# Sheet1.net
KiCad netlist of a schematic drawn in Altium Designer
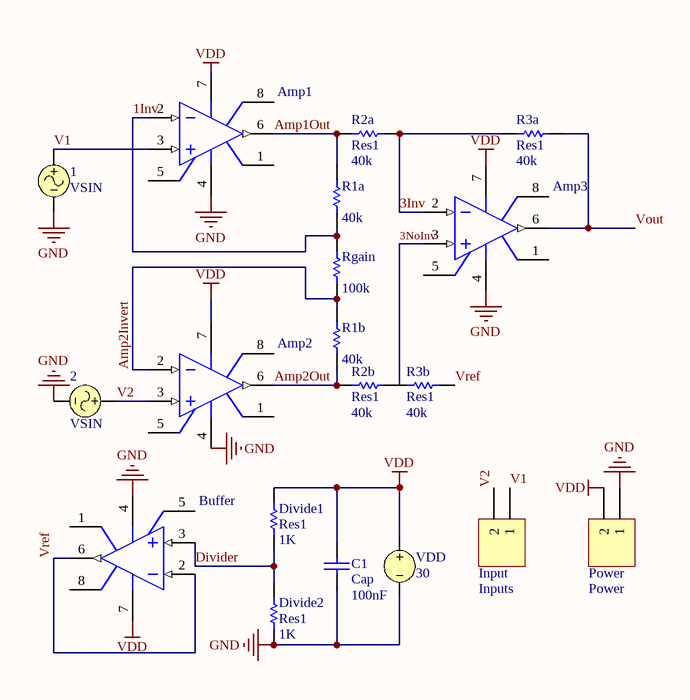
[diagram p0: Sheet1.SchDoc]

(export (version "E")
  (design (tool "Eeschema 10.0.6"))
  (components
    (comp (ref "1")
      (value "VSIN")
      (description "Sinusoidal Voltage Source")
      (fields (field (name "PUBLISHER") "Altium Limited"))
      (libsource (lib "Simulation Sources") (part "VSIN"))
    )
    (comp (ref "2")
      (value "VSIN")
      (description "Sinusoidal Voltage Source")
      (fields (field (name "PUBLISHER") "Altium Limited"))
      (libsource (lib "Simulation Sources") (part "VSIN"))
    )
    (comp (ref "Amp1")
      (value "Op Amp")
      (footprint "H-08A")
      (description "FET Operational Amplifier")
      (fields (field (name "PUBLISHER") "Altium Limited"))
      (libsource (lib "Miscellaneous Devices") (part "Op Amp"))
    )
    (comp (ref "Amp2")
      (value "Op Amp")
      (footprint "H-08A")
      (description "FET Operational Amplifier")
      (fields (field (name "PUBLISHER") "Altium Limited"))
      (libsource (lib "Miscellaneous Devices") (part "Op Amp"))
    )
    (comp (ref "Amp3")
      (value "Op Amp")
      (footprint "H-08A")
      (description "FET Operational Amplifier")
      (fields (field (name "PUBLISHER") "Altium Limited"))
      (libsource (lib "Miscellaneous Devices") (part "Op Amp"))
    )
    (comp (ref "Buffer")
      (value "Op Amp")
      (footprint "H-08A")
      (description "FET Operational Amplifier")
      (fields (field (name "PUBLISHER") "Altium Limited"))
      (libsource (lib "Miscellaneous Devices") (part "Op Amp"))
    )
    (comp (ref "C1")
      (value "Cap")
      (footprint "RAD-0.3")
      (description "Capacitor")
      (fields (field (name "ALTIUM_VALUE") "100nF") (field (name "PUBLISHER") "Altium Limited"))
      (libsource (lib "Miscellaneous Devices") (part "Cap"))
    )
    (comp (ref "Divide1")
      (value "Res1")
      (footprint "AXIAL-0.3")
      (description "Resistor")
      (fields (field (name "ALTIUM_VALUE") "1K") (field (name "PUBLISHER") "Altium Limited"))
      (libsource (lib "Miscellaneous Devices") (part "Res1"))
    )
    (comp (ref "Divide2")
      (value "Res1")
      (footprint "AXIAL-0.3")
      (description "Resistor")
      (fields (field (name "ALTIUM_VALUE") "1K") (field (name "PUBLISHER") "Altium Limited"))
      (libsource (lib "Miscellaneous Devices") (part "Res1"))
    )
    (comp (ref "Input")
      (value "Inputs")
      (footprint "HDR1X2")
      (description "Header, 2-Pin")
      (fields (field (name "PUBLISHER") "Altium Limited"))
      (libsource (lib "Miscellaneous Connectors") (part "Header 2"))
    )
    (comp (ref "Power")
      (value "Power")
      (footprint "HDR1X2")
      (description "Header, 2-Pin")
      (fields (field (name "PUBLISHER") "Altium Limited"))
      (libsource (lib "Miscellaneous Connectors") (part "Header 2"))
    )
    (comp (ref "R1a")
      (value "40k")
      (footprint "AXIAL-0.3")
      (description "Resistor")
      (fields (field (name "PUBLISHER") "Altium Limited"))
      (libsource (lib "Miscellaneous Devices") (part "Res1"))
    )
    (comp (ref "R1b")
      (value "40k")
      (footprint "AXIAL-0.3")
      (description "Resistor")
      (fields (field (name "PUBLISHER") "Altium Limited"))
      (libsource (lib "Miscellaneous Devices") (part "Res1"))
    )
    (comp (ref "R2a")
      (value "Res1")
      (footprint "AXIAL-0.3")
      (description "Resistor")
      (fields (field (name "ALTIUM_VALUE") "40k") (field (name "PUBLISHER") "Altium Limited"))
      (libsource (lib "Miscellaneous Devices") (part "Res1"))
    )
    (comp (ref "R2b")
      (value "Res1")
      (footprint "AXIAL-0.3")
      (description "Resistor")
      (fields (field (name "ALTIUM_VALUE") "40k") (field (name "PUBLISHER") "Altium Limited"))
      (libsource (lib "Miscellaneous Devices") (part "Res1"))
    )
    (comp (ref "R3a")
      (value "Res1")
      (footprint "AXIAL-0.3")
      (description "Resistor")
      (fields (field (name "ALTIUM_VALUE") "40k") (field (name "PUBLISHER") "Altium Limited"))
      (libsource (lib "Miscellaneous Devices") (part "Res1"))
    )
    (comp (ref "R3b")
      (value "Res1")
      (footprint "AXIAL-0.3")
      (description "Resistor")
      (fields (field (name "ALTIUM_VALUE") "40k") (field (name "PUBLISHER") "Altium Limited"))
      (libsource (lib "Miscellaneous Devices") (part "Res1"))
    )
    (comp (ref "Rgain")
      (value "100k")
      (footprint "AXIAL-0.3")
      (description "Resistor")
      (fields (field (name "PUBLISHER") "Altium Limited"))
      (libsource (lib "Miscellaneous Devices") (part "Res1"))
    )
    (comp (ref "VDD")
      (value "30")
      (description "Voltage Source")
      (fields (field (name "PUBLISHER") "Altium Limited"))
      (libsource (lib "Simulation Sources") (part "VSRC"))
    )
  )
  (nets
    (net (code "1") (name "/1Inv") (class "Default")
      (node (ref "Amp1") (pin "2") (pinfunction "IN-_2") (pintype "input"))
      (node (ref "R1a") (pin "1") (pinfunction "1_1") (pintype "passive"))
      (node (ref "Rgain") (pin "2") (pinfunction "2_2") (pintype "passive"))
    )
    (net (code "2") (name "/3Inv") (class "Default")
      (node (ref "Amp3") (pin "2") (pinfunction "IN-_2") (pintype "input"))
      (node (ref "R2a") (pin "2") (pinfunction "2_2") (pintype "passive"))
      (node (ref "R3a") (pin "1") (pinfunction "1_1") (pintype "passive"))
    )
    (net (code "3") (name "/3NoInv") (class "Default")
      (node (ref "Amp3") (pin "3") (pinfunction "IN+_3") (pintype "input"))
      (node (ref "R2b") (pin "2") (pinfunction "2_2") (pintype "passive"))
    )
    (net (code "4") (name "/Amp1Out") (class "Default")
      (node (ref "Amp1") (pin "6") (pinfunction "OUT_6") (pintype "output"))
      (node (ref "R1a") (pin "2") (pinfunction "2_2") (pintype "passive"))
      (node (ref "R2a") (pin "1") (pinfunction "1_1") (pintype "passive"))
    )
    (net (code "5") (name "/Amp2Invert") (class "Default")
      (node (ref "Amp2") (pin "2") (pinfunction "IN-_2") (pintype "input"))
      (node (ref "R1b") (pin "2") (pinfunction "2_2") (pintype "passive"))
      (node (ref "Rgain") (pin "1") (pinfunction "1_1") (pintype "passive"))
    )
    (net (code "6") (name "/Amp2Out") (class "Default")
      (node (ref "Amp2") (pin "6") (pinfunction "OUT_6") (pintype "output"))
      (node (ref "R1b") (pin "1") (pinfunction "1_1") (pintype "passive"))
      (node (ref "R2b") (pin "1") (pinfunction "1_1") (pintype "passive"))
    )
    (net (code "7") (name "/Divider") (class "Default")
      (node (ref "Buffer") (pin "3") (pinfunction "IN+_3") (pintype "input"))
      (node (ref "Divide1") (pin "1") (pinfunction "1_1") (pintype "passive"))
      (node (ref "Divide2") (pin "2") (pinfunction "2_2") (pintype "passive"))
    )
    (net (code "8") (name "/V1") (class "Default")
      (node (ref "1") (pin "1") (pinfunction "1_1") (pintype "passive"))
      (node (ref "Amp1") (pin "3") (pinfunction "IN+_3") (pintype "input"))
      (node (ref "Input") (pin "1") (pinfunction "1_1") (pintype "passive"))
    )
    (net (code "9") (name "/V2") (class "Default")
      (node (ref "2") (pin "1") (pinfunction "1_1") (pintype "passive"))
      (node (ref "Amp2") (pin "3") (pinfunction "IN+_3") (pintype "input"))
      (node (ref "Input") (pin "2") (pinfunction "2_2") (pintype "passive"))
    )
    (net (code "10") (name "/Vout") (class "Default")
      (node (ref "Amp3") (pin "6") (pinfunction "OUT_6") (pintype "output"))
      (node (ref "R3a") (pin "2") (pinfunction "2_2") (pintype "passive"))
    )
    (net (code "11") (name "/Vref") (class "Default")
      (node (ref "Buffer") (pin "2") (pinfunction "IN-_2") (pintype "input"))
      (node (ref "Buffer") (pin "6") (pinfunction "OUT_6") (pintype "output"))
      (node (ref "R3b") (pin "2") (pinfunction "2_2") (pintype "passive"))
    )
    (net (code "12") (name "GND") (class "Default")
      (node (ref "1") (pin "2") (pinfunction "2_2") (pintype "passive"))
      (node (ref "2") (pin "2") (pinfunction "2_2") (pintype "passive"))
      (node (ref "Amp1") (pin "4") (pinfunction "V-_4") (pintype "power_in"))
      (node (ref "Amp2") (pin "4") (pinfunction "V-_4") (pintype "power_in"))
      (node (ref "Amp3") (pin "4") (pinfunction "V-_4") (pintype "power_in"))
      (node (ref "Buffer") (pin "4") (pinfunction "V-_4") (pintype "power_in"))
      (node (ref "C1") (pin "2") (pinfunction "2_2") (pintype "passive"))
      (node (ref "Divide2") (pin "1") (pinfunction "1_1") (pintype "passive"))
      (node (ref "Power") (pin "1") (pinfunction "1_1") (pintype "passive"))
      (node (ref "VDD") (pin "2") (pinfunction "2_2") (pintype "passive"))
    )
    (net (code "13") (name "VDD") (class "Default")
      (node (ref "Amp1") (pin "7") (pinfunction "V+_7") (pintype "power_in"))
      (node (ref "Amp2") (pin "7") (pinfunction "V+_7") (pintype "power_in"))
      (node (ref "Amp3") (pin "7") (pinfunction "V+_7") (pintype "power_in"))
      (node (ref "Buffer") (pin "7") (pinfunction "V+_7") (pintype "power_in"))
      (node (ref "C1") (pin "1") (pinfunction "1_1") (pintype "passive"))
      (node (ref "Divide1") (pin "2") (pinfunction "2_2") (pintype "passive"))
      (node (ref "Power") (pin "2") (pinfunction "2_2") (pintype "passive"))
      (node (ref "VDD") (pin "1") (pinfunction "1_1") (pintype "passive"))
    )
    (net (code "14") (name "unconnected-(Amp1-OS_NUL-Pad1)") (class "Default")
      (node (ref "Amp1") (pin "1") (pinfunction "OS_NUL_1") (pintype "passive"))
    )
    (net (code "15") (name "unconnected-(Amp1-OS_NUL-Pad5)") (class "Default")
      (node (ref "Amp1") (pin "5") (pinfunction "OS_NUL_5") (pintype "passive"))
    )
    (net (code "16") (name "unconnected-(Amp1-TAB-Pad8)") (class "Default")
      (node (ref "Amp1") (pin "8") (pinfunction "TAB_8") (pintype "passive"))
    )
    (net (code "17") (name "unconnected-(Amp2-OS_NUL-Pad1)") (class "Default")
      (node (ref "Amp2") (pin "1") (pinfunction "OS_NUL_1") (pintype "passive"))
    )
    (net (code "18") (name "unconnected-(Amp2-OS_NUL-Pad5)") (class "Default")
      (node (ref "Amp2") (pin "5") (pinfunction "OS_NUL_5") (pintype "passive"))
    )
    (net (code "19") (name "unconnected-(Amp2-TAB-Pad8)") (class "Default")
      (node (ref "Amp2") (pin "8") (pinfunction "TAB_8") (pintype "passive"))
    )
    (net (code "20") (name "unconnected-(Amp3-OS_NUL-Pad1)") (class "Default")
      (node (ref "Amp3") (pin "1") (pinfunction "OS_NUL_1") (pintype "passive"))
    )
    (net (code "21") (name "unconnected-(Amp3-OS_NUL-Pad5)") (class "Default")
      (node (ref "Amp3") (pin "5") (pinfunction "OS_NUL_5") (pintype "passive"))
    )
    (net (code "22") (name "unconnected-(Amp3-TAB-Pad8)") (class "Default")
      (node (ref "Amp3") (pin "8") (pinfunction "TAB_8") (pintype "passive"))
    )
    (net (code "23") (name "unconnected-(Buffer-OS_NUL-Pad1)") (class "Default")
      (node (ref "Buffer") (pin "1") (pinfunction "OS_NUL_1") (pintype "passive"))
    )
    (net (code "24") (name "unconnected-(Buffer-OS_NUL-Pad5)") (class "Default")
      (node (ref "Buffer") (pin "5") (pinfunction "OS_NUL_5") (pintype "passive"))
    )
    (net (code "25") (name "unconnected-(Buffer-TAB-Pad8)") (class "Default")
      (node (ref "Buffer") (pin "8") (pinfunction "TAB_8") (pintype "passive"))
    )
    (net (code "26") (name "unconnected-(R3b-Pad1)") (class "Default")
      (node (ref "R3b") (pin "1") (pinfunction "1_1") (pintype "passive"))
    )
  )
)
